# Others.net
KiCad netlist of a schematic drawn in Altium Designer
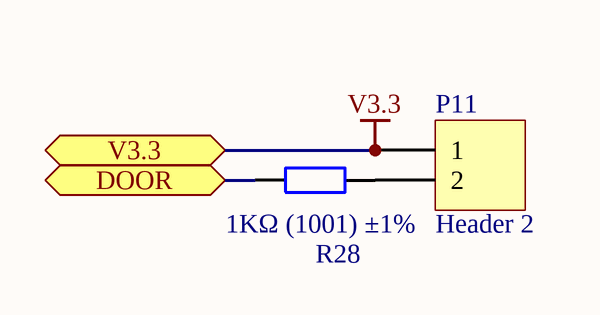
[diagram p0: Others.SchDoc]

(export (version "E")
  (design (tool "Eeschema 10.0.6"))
  (components
    (comp (ref "P11")
      (value "Header 2")
      (footprint "2P_XH2.54")
      (description "Header, 2-Pin")
      (fields (field (name "PUBLISHER") "Altium Limited"))
      (libsource (lib "Miscellaneous Connectors") (part "Header 2"))
    )
    (comp (ref "R28")
      (value "1KΩ (1001) ±1%")
      (footprint "0805_R")
      (description "贴片电阻")
      (libsource (lib "Miscellaneous Devices LC") (part "0805 1KΩ (1001) 1%"))
    )
  )
  (nets
    (net (code "1") (name "/DOOR") (class "Default")
      (node (ref "R28") (pin "1") (pinfunction "1_1") (pintype "passive"))
    )
    (net (code "2") (name "Net-(P11-Pad2)") (class "Default")
      (node (ref "P11") (pin "2") (pinfunction "2_2") (pintype "passive"))
      (node (ref "R28") (pin "2") (pinfunction "2_2") (pintype "passive"))
    )
    (net (code "3") (name "V3.3") (class "Default")
      (node (ref "P11") (pin "1") (pinfunction "1_1") (pintype "passive"))
    )
  )
)
